# ADS1110.net
KiCad netlist of a schematic drawn in EAGLE
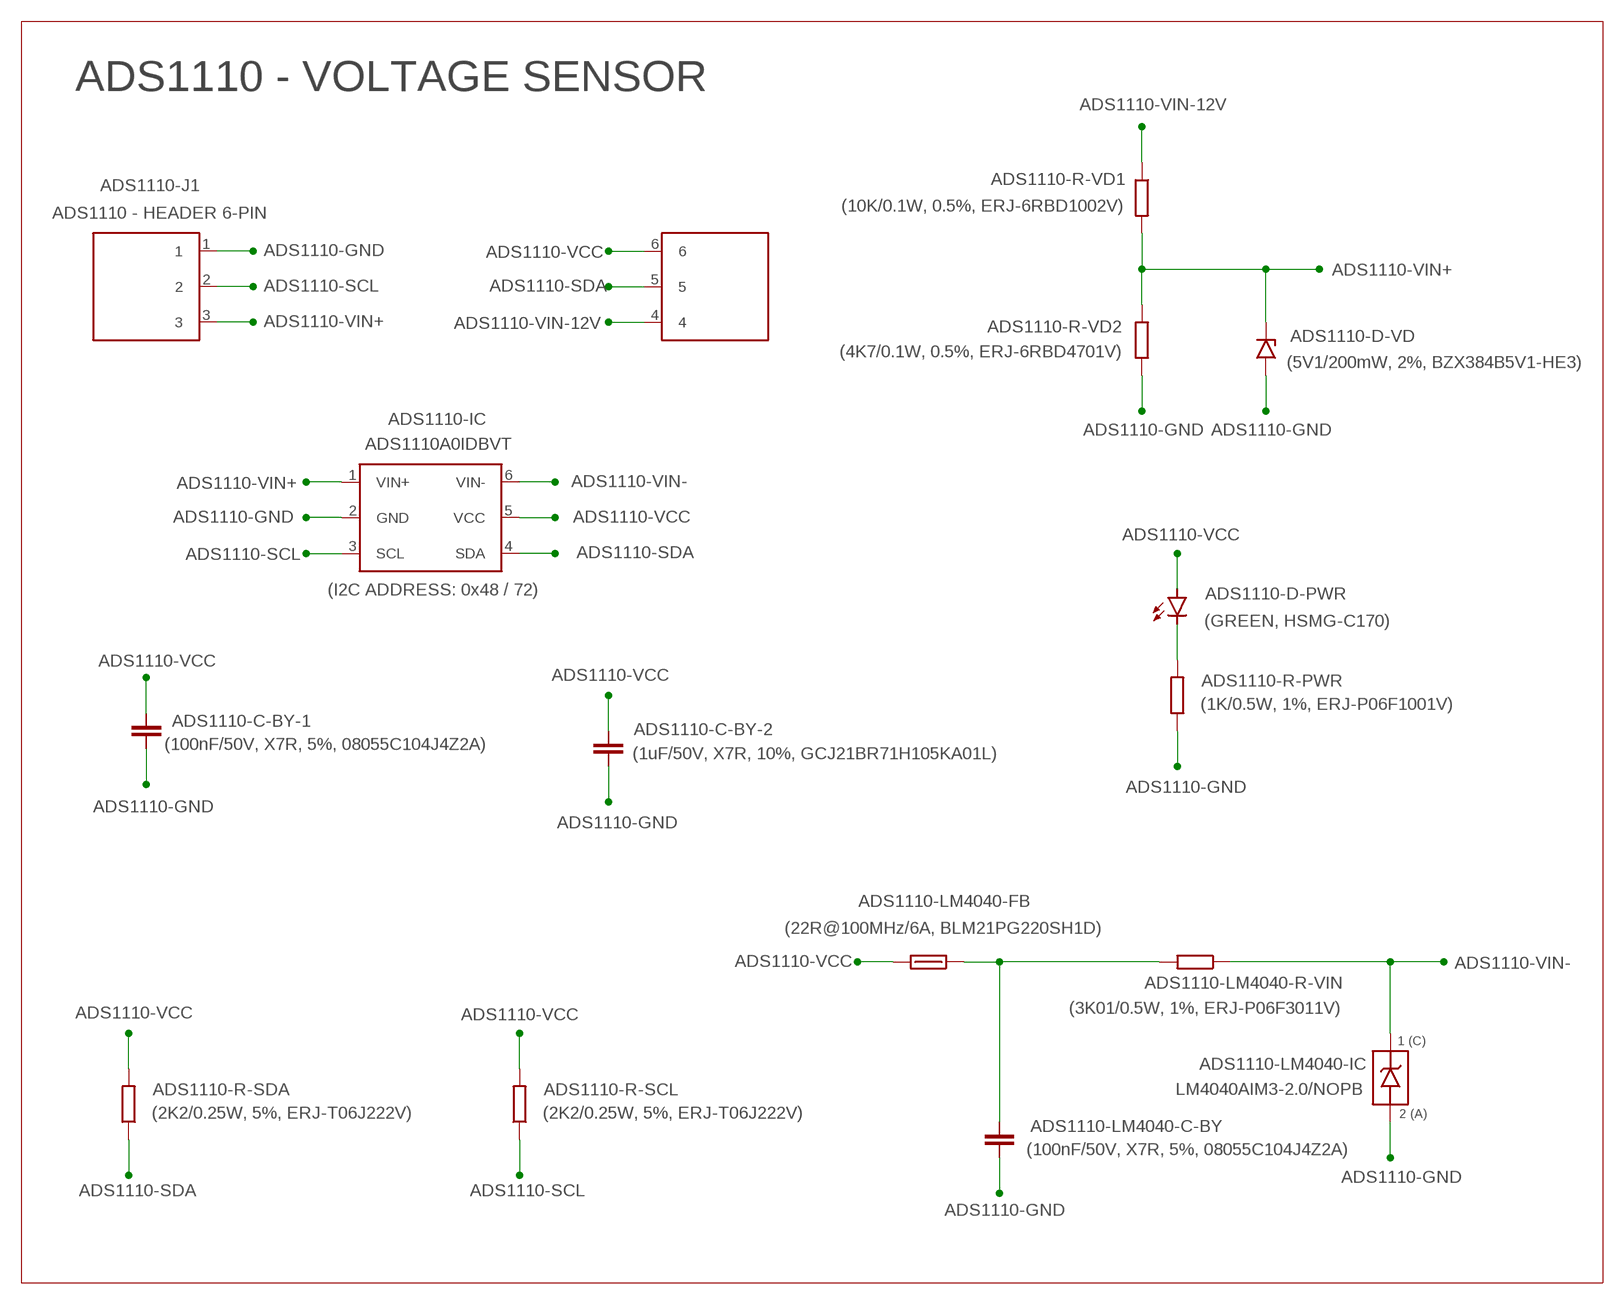
[diagram p0: schematic, sheet 1]

(export (version "E")
  (design (tool "Eeschema 10.0.6"))
  (components
    (comp (ref "ADS1110-C-BY-1")
      (value "(100nF/50V, X7R, 5%, 08055C104J4Z2A)")
      (footprint "eagle-import:0805")
      (libsource (lib "eagle-import") (part "08055C104J4Z2A"))
    )
    (comp (ref "ADS1110-C-BY-2")
      (value "(1uF/50V, X7R, 10%, GCJ21BR71H105KA01L)")
      (footprint "eagle-import:0805")
      (libsource (lib "eagle-import") (part "GCJ21BR71H105KA01L"))
    )
    (comp (ref "ADS1110-D-PWR")
      (value "(GREEN, HSMG-C170)")
      (footprint "eagle-import:DIODE_0805")
      (libsource (lib "eagle-import") (part "HSMG-C170"))
    )
    (comp (ref "ADS1110-D-VD")
      (value "(5V1/200mW, 2%, BZX384B5V1-HE3)")
      (footprint "eagle-import:SOD-323-DIODE")
      (libsource (lib "eagle-import") (part "BZX384B5V1-HE3"))
    )
    (comp (ref "ADS1110-IC")
      (value "ADS1110A0IDBVT")
      (footprint "eagle-import:SOT-457-6")
      (libsource (lib "eagle-import") (part "ADS1110A0IDBVT"))
    )
    (comp (ref "ADS1110-J1")
      (value "ADS1110 - HEADER 6-PIN")
      (footprint "eagle-import:HEADER_2.54MM_6_PIN_VER")
      (libsource (lib "eagle-import") (part "HEADER_6_PIN"))
    )
    (comp (ref "ADS1110-LM4040-C-BY")
      (value "(100nF/50V, X7R, 5%, 08055C104J4Z2A)")
      (footprint "eagle-import:0805")
      (libsource (lib "eagle-import") (part "08055C104J4Z2A"))
    )
    (comp (ref "ADS1110-LM4040-FB")
      (value "(22R@100MHz/6A, BLM21PG220SH1D)")
      (footprint "eagle-import:0805")
      (libsource (lib "eagle-import") (part "BLM21PG220SH1D"))
    )
    (comp (ref "ADS1110-LM4040-IC")
      (value "LM4040AIM3-2.0/NOPB")
      (footprint "eagle-import:SOT-23-3")
      (libsource (lib "eagle-import") (part "LM4040AIM3-2.0/NOPB"))
    )
    (comp (ref "ADS1110-LM4040-R-VIN")
      (value "(3K01/0.5W, 1%, ERJ-P06F3011V)")
      (footprint "eagle-import:0805")
      (libsource (lib "eagle-import") (part "ERJ-P06F3011V"))
    )
    (comp (ref "ADS1110-R-PWR")
      (value "(1K/0.5W, 1%, ERJ-P06F1001V)")
      (footprint "eagle-import:0805")
      (libsource (lib "eagle-import") (part "ERJ-P06F1001V"))
    )
    (comp (ref "ADS1110-R-SCL")
      (value "(2K2/0.25W, 5%, ERJ-T06J222V)")
      (footprint "eagle-import:0805")
      (libsource (lib "eagle-import") (part "ERJ-T06J222V"))
    )
    (comp (ref "ADS1110-R-SDA")
      (value "(2K2/0.25W, 5%, ERJ-T06J222V)")
      (footprint "eagle-import:0805")
      (libsource (lib "eagle-import") (part "ERJ-T06J222V"))
    )
    (comp (ref "ADS1110-R-VD1")
      (value "(10K/0.1W, 0.5%, ERJ-6RBD1002V)")
      (footprint "eagle-import:0805")
      (libsource (lib "eagle-import") (part "ERJ-6RBD1002V"))
    )
    (comp (ref "ADS1110-R-VD2")
      (value "(4K7/0.1W, 0.5%, ERJ-6RBD4701V)")
      (footprint "eagle-import:0805")
      (libsource (lib "eagle-import") (part "ERJ-6RBD4701V"))
    )
  )
  (nets
    (net (code "1") (name "/ADS1110-GND") (class "Default")
      (node (ref "ADS1110-C-BY-1") (pin "2") (pinfunction "C_2") (pintype "passive"))
      (node (ref "ADS1110-C-BY-2") (pin "1") (pinfunction "A_1") (pintype "passive"))
      (node (ref "ADS1110-D-VD") (pin "A") (pinfunction "A_A") (pintype "passive"))
      (node (ref "ADS1110-IC") (pin "2") (pinfunction "GND_2") (pintype "power_in"))
      (node (ref "ADS1110-J1") (pin "1") (pinfunction "1_1") (pintype "bidirectional"))
      (node (ref "ADS1110-LM4040-C-BY") (pin "2") (pinfunction "C_2") (pintype "passive"))
      (node (ref "ADS1110-LM4040-IC") (pin "2") (pinfunction "A_2") (pintype "passive"))
      (node (ref "ADS1110-LM4040-IC") (pin "3") (pinfunction "A_3") (pintype "passive"))
      (node (ref "ADS1110-R-PWR") (pin "1") (pinfunction "1_1") (pintype "passive"))
      (node (ref "ADS1110-R-VD2") (pin "2") (pinfunction "2_2") (pintype "passive"))
    )
    (net (code "2") (name "/ADS1110-SCL") (class "Default")
      (node (ref "ADS1110-IC") (pin "3") (pinfunction "SCL_3") (pintype "bidirectional"))
      (node (ref "ADS1110-J1") (pin "2") (pinfunction "2_2") (pintype "bidirectional"))
      (node (ref "ADS1110-R-SCL") (pin "1") (pinfunction "1_1") (pintype "passive"))
    )
    (net (code "3") (name "/ADS1110-SDA") (class "Default")
      (node (ref "ADS1110-IC") (pin "4") (pinfunction "SDA_4") (pintype "bidirectional"))
      (node (ref "ADS1110-J1") (pin "5") (pinfunction "5_5") (pintype "bidirectional"))
      (node (ref "ADS1110-R-SDA") (pin "1") (pinfunction "1_1") (pintype "passive"))
    )
    (net (code "4") (name "/ADS1110-VCC") (class "Default")
      (node (ref "ADS1110-C-BY-1") (pin "1") (pinfunction "A_1") (pintype "passive"))
      (node (ref "ADS1110-C-BY-2") (pin "2") (pinfunction "C_2") (pintype "passive"))
      (node (ref "ADS1110-D-PWR") (pin "A") (pinfunction "A_A") (pintype "passive"))
      (node (ref "ADS1110-IC") (pin "5") (pinfunction "VCC_5") (pintype "power_in"))
      (node (ref "ADS1110-J1") (pin "6") (pinfunction "6_6") (pintype "bidirectional"))
      (node (ref "ADS1110-LM4040-FB") (pin "2") (pinfunction "2_2") (pintype "passive"))
      (node (ref "ADS1110-R-SCL") (pin "2") (pinfunction "2_2") (pintype "passive"))
      (node (ref "ADS1110-R-SDA") (pin "2") (pinfunction "2_2") (pintype "passive"))
    )
    (net (code "5") (name "/ADS1110-VIN+") (class "Default")
      (node (ref "ADS1110-D-VD") (pin "C") (pinfunction "C_C") (pintype "passive"))
      (node (ref "ADS1110-IC") (pin "1") (pinfunction "VIN+_1") (pintype "bidirectional"))
      (node (ref "ADS1110-J1") (pin "3") (pinfunction "3_3") (pintype "bidirectional"))
      (node (ref "ADS1110-R-VD1") (pin "2") (pinfunction "2_2") (pintype "passive"))
      (node (ref "ADS1110-R-VD2") (pin "1") (pinfunction "1_1") (pintype "passive"))
    )
    (net (code "6") (name "/ADS1110-VIN-") (class "Default")
      (node (ref "ADS1110-IC") (pin "6") (pinfunction "VIN-_6") (pintype "bidirectional"))
      (node (ref "ADS1110-LM4040-IC") (pin "1") (pinfunction "C_1") (pintype "passive"))
      (node (ref "ADS1110-LM4040-R-VIN") (pin "1") (pinfunction "1_1") (pintype "passive"))
    )
    (net (code "7") (name "/ADS1110-VIN-12V") (class "Default")
      (node (ref "ADS1110-J1") (pin "4") (pinfunction "4_4") (pintype "bidirectional"))
      (node (ref "ADS1110-R-VD1") (pin "1") (pinfunction "1_1") (pintype "passive"))
    )
    (net (code "8") (name "Net-(ADS1110-D-PWR-PadC)") (class "Default")
      (node (ref "ADS1110-D-PWR") (pin "C") (pinfunction "C_C") (pintype "passive"))
      (node (ref "ADS1110-R-PWR") (pin "2") (pinfunction "2_2") (pintype "passive"))
    )
    (net (code "9") (name "Net-(ADS1110-LM4040-C-BY-A)") (class "Default")
      (node (ref "ADS1110-LM4040-C-BY") (pin "1") (pinfunction "A_1") (pintype "passive"))
      (node (ref "ADS1110-LM4040-FB") (pin "1") (pinfunction "1_1") (pintype "passive"))
      (node (ref "ADS1110-LM4040-R-VIN") (pin "2") (pinfunction "2_2") (pintype "passive"))
    )
  )
)
